# shield.net
KiCad netlist of a schematic drawn in EAGLE
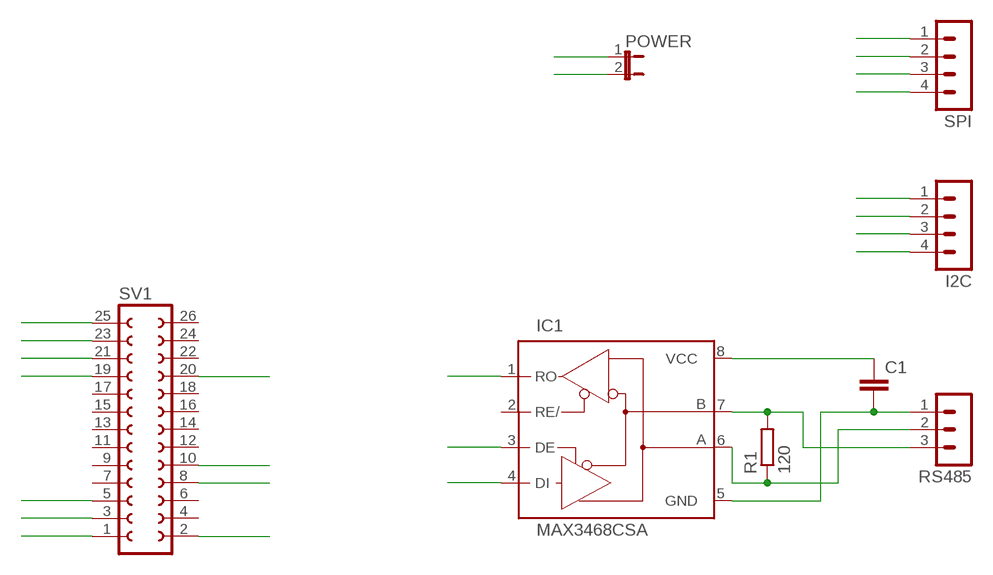
[diagram p0: schematic, sheet 1]

(export (version "E")
  (design (tool "Eeschema 10.0.6"))
  (components
    (comp (ref "C1")
      (value "C-EUC0805")
      (footprint "eagle-import:C0805")
      (libsource (lib "eagle-import") (part "C-EUC0805"))
    )
    (comp (ref "I2C")
      (value "MA04-1")
      (footprint "eagle-import:MA04-1")
      (libsource (lib "eagle-import") (part "MA04-1"))
    )
    (comp (ref "IC1")
      (value "MAX3468CSA")
      (footprint "eagle-import:SO08")
      (fields (field (name "MPN") "MAX3468CSA+"))
      (libsource (lib "eagle-import") (part "MAX34SA68C"))
    )
    (comp (ref "POWER")
      (value "JP1E")
      (footprint "eagle-import:JP1")
      (libsource (lib "eagle-import") (part "JP1E"))
    )
    (comp (ref "R1")
      (value "120")
      (footprint "eagle-import:0207_2V")
      (libsource (lib "eagle-import") (part "R-EU_0207/2V"))
    )
    (comp (ref "RS485")
      (value "MA03-1")
      (footprint "eagle-import:MA03-1")
      (libsource (lib "eagle-import") (part "MA03-1"))
    )
    (comp (ref "SPI")
      (value "MA04-1")
      (footprint "eagle-import:MA04-1")
      (libsource (lib "eagle-import") (part "MA04-1"))
    )
    (comp (ref "SV1")
      (value "FE13-2")
      (footprint "eagle-import:FE13-2")
      (libsource (lib "eagle-import") (part "FE13-2"))
    )
  )
  (nets
    (net (code "1") (name "/3V3") (class "Default")
      (node (ref "C1") (pin "1") (pinfunction "1_1") (pintype "passive"))
      (node (ref "IC1") (pin "3") (pinfunction "DE_3") (pintype "input"))
      (node (ref "IC1") (pin "8") (pinfunction "VCC_8") (pintype "power_in"))
      (node (ref "SV1") (pin "1") (pinfunction "1_1") (pintype "passive"))
    )
    (net (code "2") (name "/5V0") (class "Default")
      (node (ref "I2C") (pin "4") (pinfunction "4_4") (pintype "passive"))
      (node (ref "POWER") (pin "2") (pinfunction "2_2") (pintype "passive"))
      (node (ref "SV1") (pin "2") (pinfunction "2_2") (pintype "passive"))
    )
    (net (code "3") (name "/GND") (class "Default")
      (node (ref "C1") (pin "2") (pinfunction "2_2") (pintype "passive"))
      (node (ref "I2C") (pin "1") (pinfunction "1_1") (pintype "passive"))
      (node (ref "IC1") (pin "5") (pinfunction "GND_5") (pintype "power_in"))
      (node (ref "POWER") (pin "1") (pinfunction "1_1") (pintype "passive"))
      (node (ref "RS485") (pin "1") (pinfunction "1_1") (pintype "passive"))
      (node (ref "SPI") (pin "1") (pinfunction "1_1") (pintype "passive"))
      (node (ref "SV1") (pin "20") (pinfunction "20_20") (pintype "passive"))
      (node (ref "SV1") (pin "25") (pinfunction "25_25") (pintype "passive"))
    )
    (net (code "4") (name "/MISO") (class "Default")
      (node (ref "SPI") (pin "3") (pinfunction "3_3") (pintype "passive"))
      (node (ref "SV1") (pin "21") (pinfunction "21_21") (pintype "passive"))
    )
    (net (code "5") (name "/MOSI") (class "Default")
      (node (ref "SPI") (pin "2") (pinfunction "2_2") (pintype "passive"))
      (node (ref "SV1") (pin "19") (pinfunction "19_19") (pintype "passive"))
    )
    (net (code "6") (name "/RX") (class "Default")
      (node (ref "IC1") (pin "1") (pinfunction "RO_1") (pintype "output"))
      (node (ref "SV1") (pin "10") (pinfunction "10_10") (pintype "passive"))
    )
    (net (code "7") (name "/SCL") (class "Default")
      (node (ref "I2C") (pin "2") (pinfunction "2_2") (pintype "passive"))
      (node (ref "SV1") (pin "5") (pinfunction "5_5") (pintype "passive"))
    )
    (net (code "8") (name "/SCLK") (class "Default")
      (node (ref "SPI") (pin "4") (pinfunction "4_4") (pintype "passive"))
      (node (ref "SV1") (pin "23") (pinfunction "23_23") (pintype "passive"))
    )
    (net (code "9") (name "/SDA") (class "Default")
      (node (ref "I2C") (pin "3") (pinfunction "3_3") (pintype "passive"))
      (node (ref "SV1") (pin "3") (pinfunction "3_3") (pintype "passive"))
    )
    (net (code "10") (name "/TX") (class "Default")
      (node (ref "IC1") (pin "4") (pinfunction "DI_4") (pintype "input"))
      (node (ref "SV1") (pin "8") (pinfunction "8_8") (pintype "passive"))
    )
    (net (code "11") (name "Net-(IC1-A)") (class "Default")
      (node (ref "IC1") (pin "6") (pinfunction "A_6") (pintype "passive"))
      (node (ref "R1") (pin "1") (pinfunction "1_1") (pintype "passive"))
      (node (ref "RS485") (pin "2") (pinfunction "2_2") (pintype "passive"))
    )
    (net (code "12") (name "Net-(IC1-B)") (class "Default")
      (node (ref "IC1") (pin "7") (pinfunction "B_7") (pintype "passive"))
      (node (ref "R1") (pin "2") (pinfunction "2_2") (pintype "passive"))
      (node (ref "RS485") (pin "3") (pinfunction "3_3") (pintype "passive"))
    )
    (net (code "13") (name "unconnected-(IC1-RE{slash}-Pad2)") (class "Default")
      (node (ref "IC1") (pin "2") (pinfunction "RE/_2") (pintype "input"))
    )
    (net (code "14") (name "unconnected-(SV1-Pad4)") (class "Default")
      (node (ref "SV1") (pin "4") (pinfunction "4_4") (pintype "passive"))
    )
    (net (code "15") (name "unconnected-(SV1-Pad6)") (class "Default")
      (node (ref "SV1") (pin "6") (pinfunction "6_6") (pintype "passive"))
    )
    (net (code "16") (name "unconnected-(SV1-Pad7)") (class "Default")
      (node (ref "SV1") (pin "7") (pinfunction "7_7") (pintype "passive"))
    )
    (net (code "17") (name "unconnected-(SV1-Pad9)") (class "Default")
      (node (ref "SV1") (pin "9") (pinfunction "9_9") (pintype "passive"))
    )
    (net (code "18") (name "unconnected-(SV1-Pad11)") (class "Default")
      (node (ref "SV1") (pin "11") (pinfunction "11_11") (pintype "passive"))
    )
    (net (code "19") (name "unconnected-(SV1-Pad12)") (class "Default")
      (node (ref "SV1") (pin "12") (pinfunction "12_12") (pintype "passive"))
    )
    (net (code "20") (name "unconnected-(SV1-Pad13)") (class "Default")
      (node (ref "SV1") (pin "13") (pinfunction "13_13") (pintype "passive"))
    )
    (net (code "21") (name "unconnected-(SV1-Pad14)") (class "Default")
      (node (ref "SV1") (pin "14") (pinfunction "14_14") (pintype "passive"))
    )
    (net (code "22") (name "unconnected-(SV1-Pad15)") (class "Default")
      (node (ref "SV1") (pin "15") (pinfunction "15_15") (pintype "passive"))
    )
    (net (code "23") (name "unconnected-(SV1-Pad16)") (class "Default")
      (node (ref "SV1") (pin "16") (pinfunction "16_16") (pintype "passive"))
    )
    (net (code "24") (name "unconnected-(SV1-Pad17)") (class "Default")
      (node (ref "SV1") (pin "17") (pinfunction "17_17") (pintype "passive"))
    )
    (net (code "25") (name "unconnected-(SV1-Pad18)") (class "Default")
      (node (ref "SV1") (pin "18") (pinfunction "18_18") (pintype "passive"))
    )
    (net (code "26") (name "unconnected-(SV1-Pad22)") (class "Default")
      (node (ref "SV1") (pin "22") (pinfunction "22_22") (pintype "passive"))
    )
    (net (code "27") (name "unconnected-(SV1-Pad24)") (class "Default")
      (node (ref "SV1") (pin "24") (pinfunction "24_24") (pintype "passive"))
    )
    (net (code "28") (name "unconnected-(SV1-Pad26)") (class "Default")
      (node (ref "SV1") (pin "26") (pinfunction "26_26") (pintype "passive"))
    )
  )
)
